# Joy2PS2_rev2_1.net
KiCad netlist of a schematic drawn in EAGLE
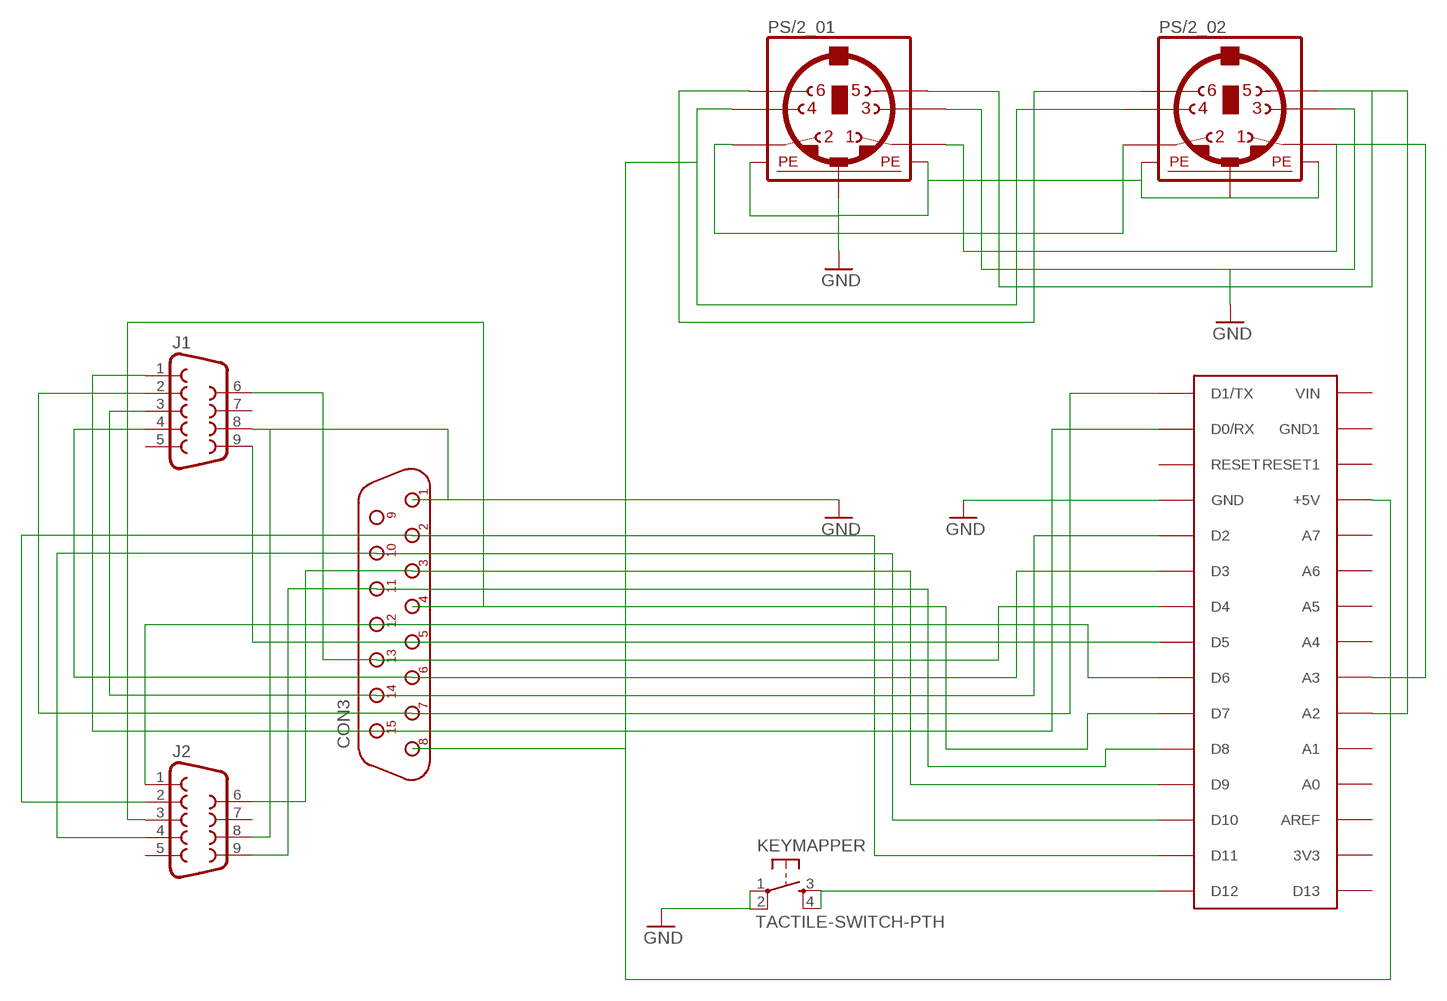
[diagram p0: schematic, sheet 1]

(export (version "E")
  (design (tool "Eeschema 10.0.6"))
  (components
    (comp (ref "ARDUINONANO")
      (value "ARDUINONANO")
      (footprint "eagle-import:PDIP-32")
      (libsource (lib "eagle-import") (part "ARDUINONANO"))
    )
    (comp (ref "CON3")
      (value "DB15M/90")
      (footprint "eagle-import:D-15M_90")
      (libsource (lib "eagle-import") (part "DB15M/90"))
    )
    (comp (ref "J1")
      (value "DB9MALE")
      (footprint "eagle-import:DB9_MALE")
      (libsource (lib "eagle-import") (part "DB9MALE"))
    )
    (comp (ref "J2")
      (value "DB9MALE")
      (footprint "eagle-import:DB9_MALE")
      (libsource (lib "eagle-import") (part "DB9MALE"))
    )
    (comp (ref "KEYMAPPER")
      (value "TACTILE-SWITCH-PTH")
      (footprint "eagle-import:TAC-SWITCH-PTH")
      (libsource (lib "eagle-import") (part "TACTILE-SWITCH-PTH"))
    )
    (comp (ref "PS/2_01")
      (value "MINI_DIN_6")
      (footprint "eagle-import:M_DIN6")
      (libsource (lib "eagle-import") (part "MINI_DIN_6"))
    )
    (comp (ref "PS/2_02")
      (value "MINI_DIN_6")
      (footprint "eagle-import:M_DIN6")
      (libsource (lib "eagle-import") (part "MINI_DIN_6"))
    )
  )
  (nets
    (net (code "1") (name "GND") (class "Default")
      (node (ref "ARDUINONANO") (pin "GND") (pinfunction "GND_GND") (pintype "bidirectional"))
      (node (ref "CON3") (pin "1") (pinfunction "1_1") (pintype "passive"))
      (node (ref "J1") (pin "8") (pinfunction "8_8") (pintype "passive"))
      (node (ref "J2") (pin "8") (pinfunction "8_8") (pintype "passive"))
      (node (ref "KEYMAPPER") (pin "1") (pinfunction "1_1") (pintype "passive"))
      (node (ref "KEYMAPPER") (pin "2") (pinfunction "2_2") (pintype "passive"))
      (node (ref "PS/2_01") (pin "3") (pinfunction "3_3") (pintype "passive"))
      (node (ref "PS/2_01") (pin "SH1") (pinfunction "PE1_SH1") (pintype "power_in"))
      (node (ref "PS/2_01") (pin "SH2") (pinfunction "PE2_SH2") (pintype "power_in"))
      (node (ref "PS/2_01") (pin "SH3") (pinfunction "PE3_SH3") (pintype "power_in"))
      (node (ref "PS/2_02") (pin "3") (pinfunction "3_3") (pintype "passive"))
      (node (ref "PS/2_02") (pin "SH1") (pinfunction "PE1_SH1") (pintype "power_in"))
      (node (ref "PS/2_02") (pin "SH2") (pinfunction "PE2_SH2") (pintype "power_in"))
      (node (ref "PS/2_02") (pin "SH3") (pinfunction "PE3_SH3") (pintype "power_in"))
    )
    (net (code "2") (name "Net-(ARDUINONANO-Pad+5V)") (class "Default")
      (node (ref "ARDUINONANO") (pin "+5V") (pinfunction "+5V_+5V") (pintype "bidirectional"))
      (node (ref "CON3") (pin "8") (pinfunction "8_8") (pintype "passive"))
      (node (ref "PS/2_01") (pin "4") (pinfunction "4_4") (pintype "passive"))
      (node (ref "PS/2_02") (pin "4") (pinfunction "4_4") (pintype "passive"))
    )
    (net (code "3") (name "Net-(ARDUINONANO-PadA2)") (class "Default")
      (node (ref "ARDUINONANO") (pin "A2") (pinfunction "A2_A2") (pintype "bidirectional"))
      (node (ref "PS/2_01") (pin "5") (pinfunction "5_5") (pintype "passive"))
      (node (ref "PS/2_02") (pin "5") (pinfunction "5_5") (pintype "passive"))
    )
    (net (code "4") (name "Net-(ARDUINONANO-PadA3)") (class "Default")
      (node (ref "ARDUINONANO") (pin "A3") (pinfunction "A3_A3") (pintype "bidirectional"))
      (node (ref "PS/2_01") (pin "1") (pinfunction "1_1") (pintype "passive"))
      (node (ref "PS/2_02") (pin "1") (pinfunction "1_1") (pintype "passive"))
    )
    (net (code "5") (name "Net-(ARDUINONANO-PadD0{slash}RX)") (class "Default")
      (node (ref "ARDUINONANO") (pin "D0/RX") (pinfunction "D0/RX_D0/RX") (pintype "bidirectional"))
      (node (ref "CON3") (pin "15") (pinfunction "15_15") (pintype "passive"))
      (node (ref "J1") (pin "1") (pinfunction "1_1") (pintype "passive"))
    )
    (net (code "6") (name "Net-(ARDUINONANO-PadD1{slash}TX)") (class "Default")
      (node (ref "ARDUINONANO") (pin "D1/TX") (pinfunction "D1/TX_D1/TX") (pintype "bidirectional"))
      (node (ref "CON3") (pin "7") (pinfunction "7_7") (pintype "passive"))
      (node (ref "J1") (pin "2") (pinfunction "2_2") (pintype "passive"))
    )
    (net (code "7") (name "Net-(ARDUINONANO-PadD2)") (class "Default")
      (node (ref "ARDUINONANO") (pin "D2") (pinfunction "D2_D2") (pintype "bidirectional"))
      (node (ref "CON3") (pin "14") (pinfunction "14_14") (pintype "passive"))
      (node (ref "J1") (pin "3") (pinfunction "3_3") (pintype "passive"))
    )
    (net (code "8") (name "Net-(ARDUINONANO-PadD3)") (class "Default")
      (node (ref "ARDUINONANO") (pin "D3") (pinfunction "D3_D3") (pintype "bidirectional"))
      (node (ref "CON3") (pin "6") (pinfunction "6_6") (pintype "passive"))
      (node (ref "J1") (pin "4") (pinfunction "4_4") (pintype "passive"))
    )
    (net (code "9") (name "Net-(ARDUINONANO-PadD4)") (class "Default")
      (node (ref "ARDUINONANO") (pin "D4") (pinfunction "D4_D4") (pintype "bidirectional"))
      (node (ref "CON3") (pin "13") (pinfunction "13_13") (pintype "passive"))
      (node (ref "J1") (pin "6") (pinfunction "6_6") (pintype "passive"))
    )
    (net (code "10") (name "Net-(ARDUINONANO-PadD5)") (class "Default")
      (node (ref "ARDUINONANO") (pin "D5") (pinfunction "D5_D5") (pintype "bidirectional"))
      (node (ref "CON3") (pin "5") (pinfunction "5_5") (pintype "passive"))
      (node (ref "J1") (pin "9") (pinfunction "9_9") (pintype "passive"))
    )
    (net (code "11") (name "Net-(ARDUINONANO-PadD6)") (class "Default")
      (node (ref "ARDUINONANO") (pin "D6") (pinfunction "D6_D6") (pintype "bidirectional"))
      (node (ref "CON3") (pin "12") (pinfunction "12_12") (pintype "passive"))
      (node (ref "J2") (pin "1") (pinfunction "1_1") (pintype "passive"))
    )
    (net (code "12") (name "Net-(ARDUINONANO-PadD7)") (class "Default")
      (node (ref "ARDUINONANO") (pin "D7") (pinfunction "D7_D7") (pintype "bidirectional"))
      (node (ref "CON3") (pin "4") (pinfunction "4_4") (pintype "passive"))
      (node (ref "J2") (pin "3") (pinfunction "3_3") (pintype "passive"))
    )
    (net (code "13") (name "Net-(ARDUINONANO-PadD8)") (class "Default")
      (node (ref "ARDUINONANO") (pin "D8") (pinfunction "D8_D8") (pintype "bidirectional"))
      (node (ref "CON3") (pin "11") (pinfunction "11_11") (pintype "passive"))
      (node (ref "J2") (pin "9") (pinfunction "9_9") (pintype "passive"))
    )
    (net (code "14") (name "Net-(ARDUINONANO-PadD9)") (class "Default")
      (node (ref "ARDUINONANO") (pin "D9") (pinfunction "D9_D9") (pintype "bidirectional"))
      (node (ref "CON3") (pin "3") (pinfunction "3_3") (pintype "passive"))
      (node (ref "J2") (pin "6") (pinfunction "6_6") (pintype "passive"))
    )
    (net (code "15") (name "Net-(ARDUINONANO-PadD10)") (class "Default")
      (node (ref "ARDUINONANO") (pin "D10") (pinfunction "D10_D10") (pintype "bidirectional"))
      (node (ref "CON3") (pin "10") (pinfunction "10_10") (pintype "passive"))
      (node (ref "J2") (pin "4") (pinfunction "4_4") (pintype "passive"))
    )
    (net (code "16") (name "Net-(ARDUINONANO-PadD11)") (class "Default")
      (node (ref "ARDUINONANO") (pin "D11") (pinfunction "D11_D11") (pintype "bidirectional"))
      (node (ref "CON3") (pin "2") (pinfunction "2_2") (pintype "passive"))
      (node (ref "J2") (pin "2") (pinfunction "2_2") (pintype "passive"))
    )
    (net (code "17") (name "Net-(ARDUINONANO-PadD12)") (class "Default")
      (node (ref "ARDUINONANO") (pin "D12") (pinfunction "D12_D12") (pintype "bidirectional"))
      (node (ref "KEYMAPPER") (pin "3") (pinfunction "3_3") (pintype "passive"))
      (node (ref "KEYMAPPER") (pin "4") (pinfunction "4_4") (pintype "passive"))
    )
    (net (code "18") (name "Net-(PS/2_01-Pad2)") (class "Default")
      (node (ref "PS/2_01") (pin "2") (pinfunction "2_2") (pintype "passive"))
      (node (ref "PS/2_02") (pin "2") (pinfunction "2_2") (pintype "passive"))
    )
    (net (code "19") (name "Net-(PS/2_01-Pad6)") (class "Default")
      (node (ref "PS/2_01") (pin "6") (pinfunction "6_6") (pintype "passive"))
      (node (ref "PS/2_02") (pin "6") (pinfunction "6_6") (pintype "passive"))
    )
    (net (code "20") (name "unconnected-(ARDUINONANO-Pad3V3)") (class "Default")
      (node (ref "ARDUINONANO") (pin "3V3") (pinfunction "3V3_3V3") (pintype "bidirectional"))
    )
    (net (code "21") (name "unconnected-(ARDUINONANO-PadA0)") (class "Default")
      (node (ref "ARDUINONANO") (pin "A0") (pinfunction "A0_A0") (pintype "bidirectional"))
    )
    (net (code "22") (name "unconnected-(ARDUINONANO-PadA1)") (class "Default")
      (node (ref "ARDUINONANO") (pin "A1") (pinfunction "A1_A1") (pintype "bidirectional"))
    )
    (net (code "23") (name "unconnected-(ARDUINONANO-PadA4)") (class "Default")
      (node (ref "ARDUINONANO") (pin "A4") (pinfunction "A4_A4") (pintype "bidirectional"))
    )
    (net (code "24") (name "unconnected-(ARDUINONANO-PadA5)") (class "Default")
      (node (ref "ARDUINONANO") (pin "A5") (pinfunction "A5_A5") (pintype "bidirectional"))
    )
    (net (code "25") (name "unconnected-(ARDUINONANO-PadA6)") (class "Default")
      (node (ref "ARDUINONANO") (pin "A6") (pinfunction "A6_A6") (pintype "bidirectional"))
    )
    (net (code "26") (name "unconnected-(ARDUINONANO-PadA7)") (class "Default")
      (node (ref "ARDUINONANO") (pin "A7") (pinfunction "A7_A7") (pintype "bidirectional"))
    )
    (net (code "27") (name "unconnected-(ARDUINONANO-PadAREF)") (class "Default")
      (node (ref "ARDUINONANO") (pin "AREF") (pinfunction "AREF_AREF") (pintype "bidirectional"))
    )
    (net (code "28") (name "unconnected-(ARDUINONANO-PadD13)") (class "Default")
      (node (ref "ARDUINONANO") (pin "D13") (pinfunction "D13_D13") (pintype "bidirectional"))
    )
    (net (code "29") (name "unconnected-(ARDUINONANO-PadGND1)") (class "Default")
      (node (ref "ARDUINONANO") (pin "GND1") (pinfunction "GND1_GND1") (pintype "bidirectional"))
    )
    (net (code "30") (name "unconnected-(ARDUINONANO-PadRESET)") (class "Default")
      (node (ref "ARDUINONANO") (pin "RESET") (pinfunction "RESET_RESET") (pintype "bidirectional"))
    )
    (net (code "31") (name "unconnected-(ARDUINONANO-PadRESET1)") (class "Default")
      (node (ref "ARDUINONANO") (pin "RESET1") (pinfunction "RESET1_RESET1") (pintype "bidirectional"))
    )
    (net (code "32") (name "unconnected-(ARDUINONANO-PadVIN)") (class "Default")
      (node (ref "ARDUINONANO") (pin "VIN") (pinfunction "VIN_VIN") (pintype "bidirectional"))
    )
    (net (code "33") (name "unconnected-(CON3-Pad9)") (class "Default")
      (node (ref "CON3") (pin "9") (pinfunction "9_9") (pintype "passive"))
    )
    (net (code "34") (name "unconnected-(J1-Pad5)") (class "Default")
      (node (ref "J1") (pin "5") (pinfunction "5_5") (pintype "passive"))
    )
    (net (code "35") (name "unconnected-(J1-Pad7)") (class "Default")
      (node (ref "J1") (pin "7") (pinfunction "7_7") (pintype "passive"))
    )
    (net (code "36") (name "unconnected-(J2-Pad5)") (class "Default")
      (node (ref "J2") (pin "5") (pinfunction "5_5") (pintype "passive"))
    )
    (net (code "37") (name "unconnected-(J2-Pad7)") (class "Default")
      (node (ref "J2") (pin "7") (pinfunction "7_7") (pintype "passive"))
    )
  )
)
